# RS485.net
KiCad netlist of a schematic drawn in Altium Designer
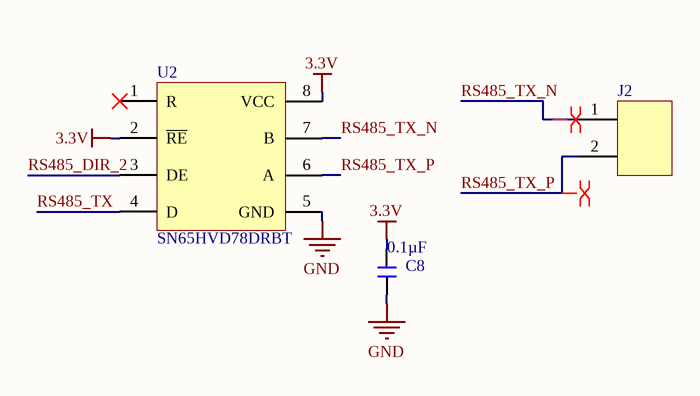
[diagram p0: RS485.SchDoc]

(export (version "E")
  (design (tool "Eeschema 10.0.6"))
  (components
    (comp (ref "C8")
      (value "0.1µF")
      (footprint "402 capacitor - duplicate")
      (description "CON SMD 402")
      (fields (field (name "MPN") "CL05A104KA5NNNC") (field (name "Comment") "0402 capacitor"))
      (libsource (lib "Schlib1") (part "CON SMD 402"))
    )
    (comp (ref "J2")
      (value "2 POS")
      (footprint "0901362102")
      (description "CONN HEADER R/A 2POS 2.54MM")
      (fields (field (name "MPN") "0901362102"))
      (libsource (lib "Schlib1") (part "0901362102"))
    )
    (comp (ref "U2")
      (value "SN65HVD78DRBT")
      (description "IC TRANSCEIVER HALF 1/1 8SON (-7V +12V - 54 Ω)")
      (libsource (lib "Schlib1") (part "SN65HVD78DRBT"))
    )
  )
  (nets
    (net (code "1") (name "/RS485_DIR_2") (class "Default")
      (node (ref "U2") (pin "3") (pinfunction "DE_3") (pintype "passive"))
    )
    (net (code "2") (name "/RS485_TX") (class "Default")
      (node (ref "U2") (pin "4") (pinfunction "D_4") (pintype "passive"))
    )
    (net (code "3") (name "/RS485_TX_N") (class "Default")
      (node (ref "J2") (pin "1") (pintype "passive"))
      (node (ref "U2") (pin "7") (pinfunction "B_7") (pintype "passive"))
    )
    (net (code "4") (name "/RS485_TX_P") (class "Default")
      (node (ref "J2") (pin "2") (pintype "passive"))
      (node (ref "U2") (pin "6") (pinfunction "A_6") (pintype "passive"))
    )
    (net (code "5") (name "3.3V") (class "Default")
      (node (ref "C8") (pin "2") (pintype "passive"))
      (node (ref "U2") (pin "2") (pinfunction "~{RE}_2") (pintype "passive"))
      (node (ref "U2") (pin "8") (pinfunction "VCC_8") (pintype "passive"))
    )
    (net (code "6") (name "GND") (class "Default")
      (node (ref "C8") (pin "1") (pintype "passive"))
      (node (ref "U2") (pin "5") (pinfunction "GND_5") (pintype "passive"))
    )
    (net (code "7") (name "unconnected-(U2-R-Pad1)") (class "Default")
      (node (ref "U2") (pin "1") (pinfunction "R_1") (pintype "passive+no_connect"))
    )
  )
)
